# radio.net
KiCad netlist of a schematic drawn in Altium Designer
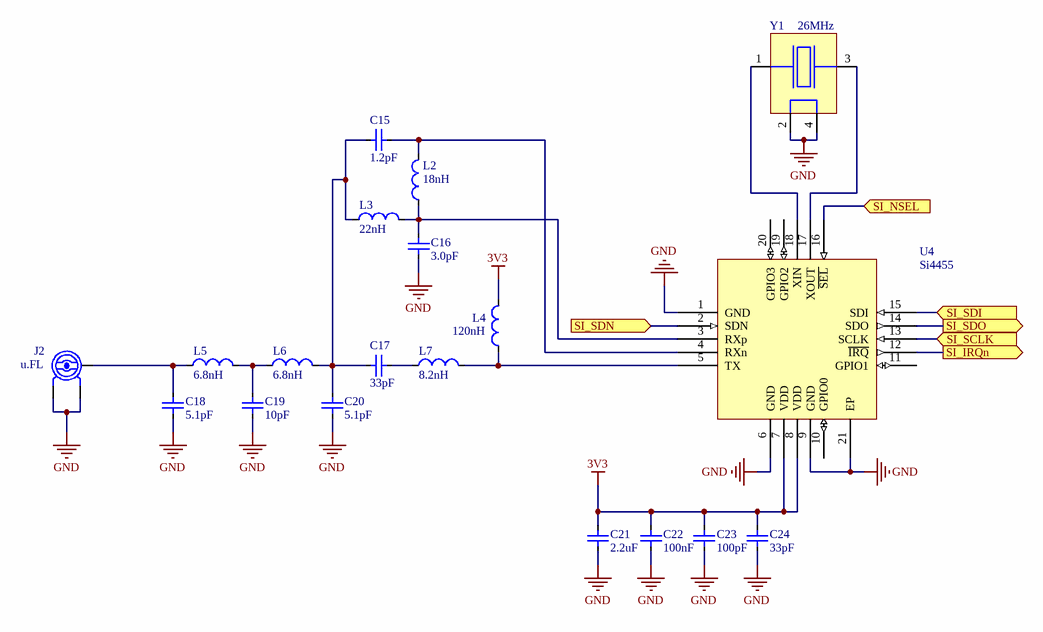
[diagram p0: radio.SchDoc]

(export (version "E")
  (design (tool "Eeschema 10.0.6"))
  (components
    (comp (ref "C15")
      (value "1.2pF")
      (footprint "0402_[1005]")
      (description "Capacitor")
      (libsource (lib "Discrete") (part "C"))
    )
    (comp (ref "C16")
      (value "3.0pF")
      (footprint "0402_[1005]")
      (description "Capacitor")
      (libsource (lib "Discrete") (part "C"))
    )
    (comp (ref "C17")
      (value "33pF")
      (footprint "0402_[1005]")
      (description "Capacitor")
      (libsource (lib "Discrete") (part "C"))
    )
    (comp (ref "C18")
      (value "5.1pF")
      (footprint "0402_[1005]")
      (description "Capacitor")
      (libsource (lib "Discrete") (part "C"))
    )
    (comp (ref "C19")
      (value "10pF")
      (footprint "0402_[1005]")
      (description "Capacitor")
      (libsource (lib "Discrete") (part "C"))
    )
    (comp (ref "C20")
      (value "5.1pF")
      (footprint "0402_[1005]")
      (description "Capacitor")
      (libsource (lib "Discrete") (part "C"))
    )
    (comp (ref "C21")
      (value "2.2uF")
      (footprint "0603_[1608]")
      (description "Capacitor")
      (libsource (lib "Discrete") (part "C"))
    )
    (comp (ref "C22")
      (value "100nF")
      (footprint "0402_[1005]")
      (description "Capacitor")
      (libsource (lib "Discrete") (part "C"))
    )
    (comp (ref "C23")
      (value "100pF")
      (footprint "0402_[1005]")
      (description "Capacitor")
      (libsource (lib "Discrete") (part "C"))
    )
    (comp (ref "C24")
      (value "33pF")
      (footprint "0402_[1005]")
      (description "Capacitor")
      (libsource (lib "Discrete") (part "C"))
    )
    (comp (ref "J2")
      (value "u.FL")
      (footprint "U.FL_COAXIAL_2.6x2.6MM_STRAIGHT_SMD")
      (description "u.FL antenna connector")
      (libsource (lib "Connectors") (part "u.FL"))
    )
    (comp (ref "L2")
      (value "18nH")
      (footprint "0402_[1005]")
      (description "Inductor")
      (libsource (lib "Discrete") (part "L"))
    )
    (comp (ref "L3")
      (value "22nH")
      (footprint "0402_[1005]")
      (description "Inductor")
      (libsource (lib "Discrete") (part "L"))
    )
    (comp (ref "L4")
      (value "120nH")
      (footprint "0402_[1005]")
      (description "Inductor")
      (libsource (lib "Discrete") (part "L"))
    )
    (comp (ref "L5")
      (value "6.8nH")
      (footprint "0402_[1005]")
      (description "Inductor")
      (libsource (lib "Discrete") (part "L"))
    )
    (comp (ref "L6")
      (value "6.8nH")
      (footprint "0402_[1005]")
      (description "Inductor")
      (libsource (lib "Discrete") (part "L"))
    )
    (comp (ref "L7")
      (value "8.2nH")
      (footprint "0402_[1005]")
      (description "Inductor")
      (libsource (lib "Discrete") (part "L"))
    )
    (comp (ref "U4")
      (value "Si4455")
      (footprint "QFN50P300X300X90_HS-21N")
      (description "Low-current OOK/(G)FSK sub-GHz transceiver")
      (libsource (lib "RF") (part "Si4455"))
    )
    (comp (ref "Y1")
      (value "26MHz")
      (footprint "CRYSTAL_2.5X2MM_4P_SMD")
      (description "Crystal oscillator, 4-pin")
      (libsource (lib "Discrete") (part "XTAL-4"))
    )
  )
  (nets
    (net (code "1") (name "/SI_IRQn") (class "Default")
      (node (ref "U4") (pin "12") (pinfunction "~{IRQ}_12") (pintype "output"))
    )
    (net (code "2") (name "/SI_NSEL") (class "Default")
      (node (ref "U4") (pin "16") (pinfunction "~{SEL}_16") (pintype "input"))
    )
    (net (code "3") (name "/SI_SCLK") (class "Default")
      (node (ref "U4") (pin "13") (pinfunction "SCLK_13") (pintype "input"))
    )
    (net (code "4") (name "/SI_SDI") (class "Default")
      (node (ref "U4") (pin "15") (pinfunction "SDI_15") (pintype "input"))
    )
    (net (code "5") (name "/SI_SDN") (class "Default")
      (node (ref "U4") (pin "2") (pinfunction "SDN_2") (pintype "input"))
    )
    (net (code "6") (name "/SI_SDO") (class "Default")
      (node (ref "U4") (pin "14") (pinfunction "SDO_14") (pintype "output"))
    )
    (net (code "7") (name "3V3") (class "Default")
      (node (ref "C21") (pin "2") (pinfunction "2_2") (pintype "passive"))
      (node (ref "C22") (pin "2") (pinfunction "2_2") (pintype "passive"))
      (node (ref "C23") (pin "2") (pinfunction "2_2") (pintype "passive"))
      (node (ref "C24") (pin "2") (pinfunction "2_2") (pintype "passive"))
      (node (ref "L4") (pin "2") (pinfunction "2_2") (pintype "passive"))
      (node (ref "U4") (pin "7") (pinfunction "VDD_7") (pintype "power_in"))
      (node (ref "U4") (pin "8") (pinfunction "VDD_8") (pintype "power_in"))
    )
    (net (code "8") (name "GND") (class "Default")
      (node (ref "C16") (pin "1") (pinfunction "1_1") (pintype "passive"))
      (node (ref "C18") (pin "1") (pinfunction "1_1") (pintype "passive"))
      (node (ref "C19") (pin "1") (pinfunction "1_1") (pintype "passive"))
      (node (ref "C20") (pin "1") (pinfunction "1_1") (pintype "passive"))
      (node (ref "C21") (pin "1") (pinfunction "1_1") (pintype "passive"))
      (node (ref "C22") (pin "1") (pinfunction "1_1") (pintype "passive"))
      (node (ref "C23") (pin "1") (pinfunction "1_1") (pintype "passive"))
      (node (ref "C24") (pin "1") (pinfunction "1_1") (pintype "passive"))
      (node (ref "J2") (pin "2") (pinfunction "GND_2") (pintype "power_in"))
      (node (ref "J2") (pin "3") (pinfunction "GND_3") (pintype "power_in"))
      (node (ref "U4") (pin "1") (pinfunction "GND_1") (pintype "power_in"))
      (node (ref "U4") (pin "21") (pinfunction "EP_21") (pintype "passive"))
      (node (ref "U4") (pin "6") (pinfunction "GND_6") (pintype "power_in"))
      (node (ref "U4") (pin "9") (pinfunction "GND_9") (pintype "power_in"))
      (node (ref "Y1") (pin "2") (pinfunction "2_2") (pintype "passive"))
      (node (ref "Y1") (pin "4") (pinfunction "4_4") (pintype "passive"))
    )
    (net (code "9") (name "Net-(C15-Pad1)") (class "Default")
      (node (ref "C15") (pin "1") (pinfunction "1_1") (pintype "passive"))
      (node (ref "C17") (pin "1") (pinfunction "1_1") (pintype "passive"))
      (node (ref "C20") (pin "2") (pinfunction "2_2") (pintype "passive"))
      (node (ref "L3") (pin "1") (pinfunction "1_1") (pintype "passive"))
      (node (ref "L6") (pin "2") (pinfunction "2_2") (pintype "passive"))
    )
    (net (code "10") (name "Net-(C17-Pad2)") (class "Default")
      (node (ref "C17") (pin "2") (pinfunction "2_2") (pintype "passive"))
      (node (ref "L7") (pin "1") (pinfunction "1_1") (pintype "passive"))
    )
    (net (code "11") (name "Net-(C19-Pad2)") (class "Default")
      (node (ref "C19") (pin "2") (pinfunction "2_2") (pintype "passive"))
      (node (ref "L5") (pin "2") (pinfunction "2_2") (pintype "passive"))
      (node (ref "L6") (pin "1") (pinfunction "1_1") (pintype "passive"))
    )
    (net (code "12") (name "Net-(J2-SIG)") (class "Default")
      (node (ref "C18") (pin "2") (pinfunction "2_2") (pintype "passive"))
      (node (ref "J2") (pin "1") (pinfunction "SIG_1") (pintype "passive"))
      (node (ref "L5") (pin "1") (pinfunction "1_1") (pintype "passive"))
    )
    (net (code "13") (name "Net-(U4-RXn)") (class "Default")
      (node (ref "C15") (pin "2") (pinfunction "2_2") (pintype "passive"))
      (node (ref "L2") (pin "2") (pinfunction "2_2") (pintype "passive"))
      (node (ref "U4") (pin "4") (pinfunction "RXn_4") (pintype "passive"))
    )
    (net (code "14") (name "Net-(U4-RXp)") (class "Default")
      (node (ref "C16") (pin "2") (pinfunction "2_2") (pintype "passive"))
      (node (ref "L2") (pin "1") (pinfunction "1_1") (pintype "passive"))
      (node (ref "L3") (pin "2") (pinfunction "2_2") (pintype "passive"))
      (node (ref "U4") (pin "3") (pinfunction "RXp_3") (pintype "passive"))
    )
    (net (code "15") (name "Net-(U4-TX)") (class "Default")
      (node (ref "L4") (pin "1") (pinfunction "1_1") (pintype "passive"))
      (node (ref "L7") (pin "2") (pinfunction "2_2") (pintype "passive"))
      (node (ref "U4") (pin "5") (pinfunction "TX_5") (pintype "passive"))
    )
    (net (code "16") (name "Net-(U4-XIN)") (class "Default")
      (node (ref "U4") (pin "18") (pinfunction "XIN_18") (pintype "passive"))
      (node (ref "Y1") (pin "1") (pinfunction "1_1") (pintype "passive"))
    )
    (net (code "17") (name "Net-(U4-XOUT)") (class "Default")
      (node (ref "U4") (pin "17") (pinfunction "XOUT_17") (pintype "passive"))
      (node (ref "Y1") (pin "3") (pinfunction "3_3") (pintype "passive"))
    )
    (net (code "18") (name "unconnected-(U4-GPIO0-Pad10)") (class "Default")
      (node (ref "U4") (pin "10") (pinfunction "GPIO0_10") (pintype "bidirectional"))
    )
    (net (code "19") (name "unconnected-(U4-GPIO1-Pad11)") (class "Default")
      (node (ref "U4") (pin "11") (pinfunction "GPIO1_11") (pintype "bidirectional"))
    )
    (net (code "20") (name "unconnected-(U4-GPIO2-Pad19)") (class "Default")
      (node (ref "U4") (pin "19") (pinfunction "GPIO2_19") (pintype "bidirectional"))
    )
    (net (code "21") (name "unconnected-(U4-GPIO3-Pad20)") (class "Default")
      (node (ref "U4") (pin "20") (pinfunction "GPIO3_20") (pintype "bidirectional"))
    )
  )
)
